# pca63557_sheet1_connectors.net
KiCad netlist of a schematic drawn in Altium Designer
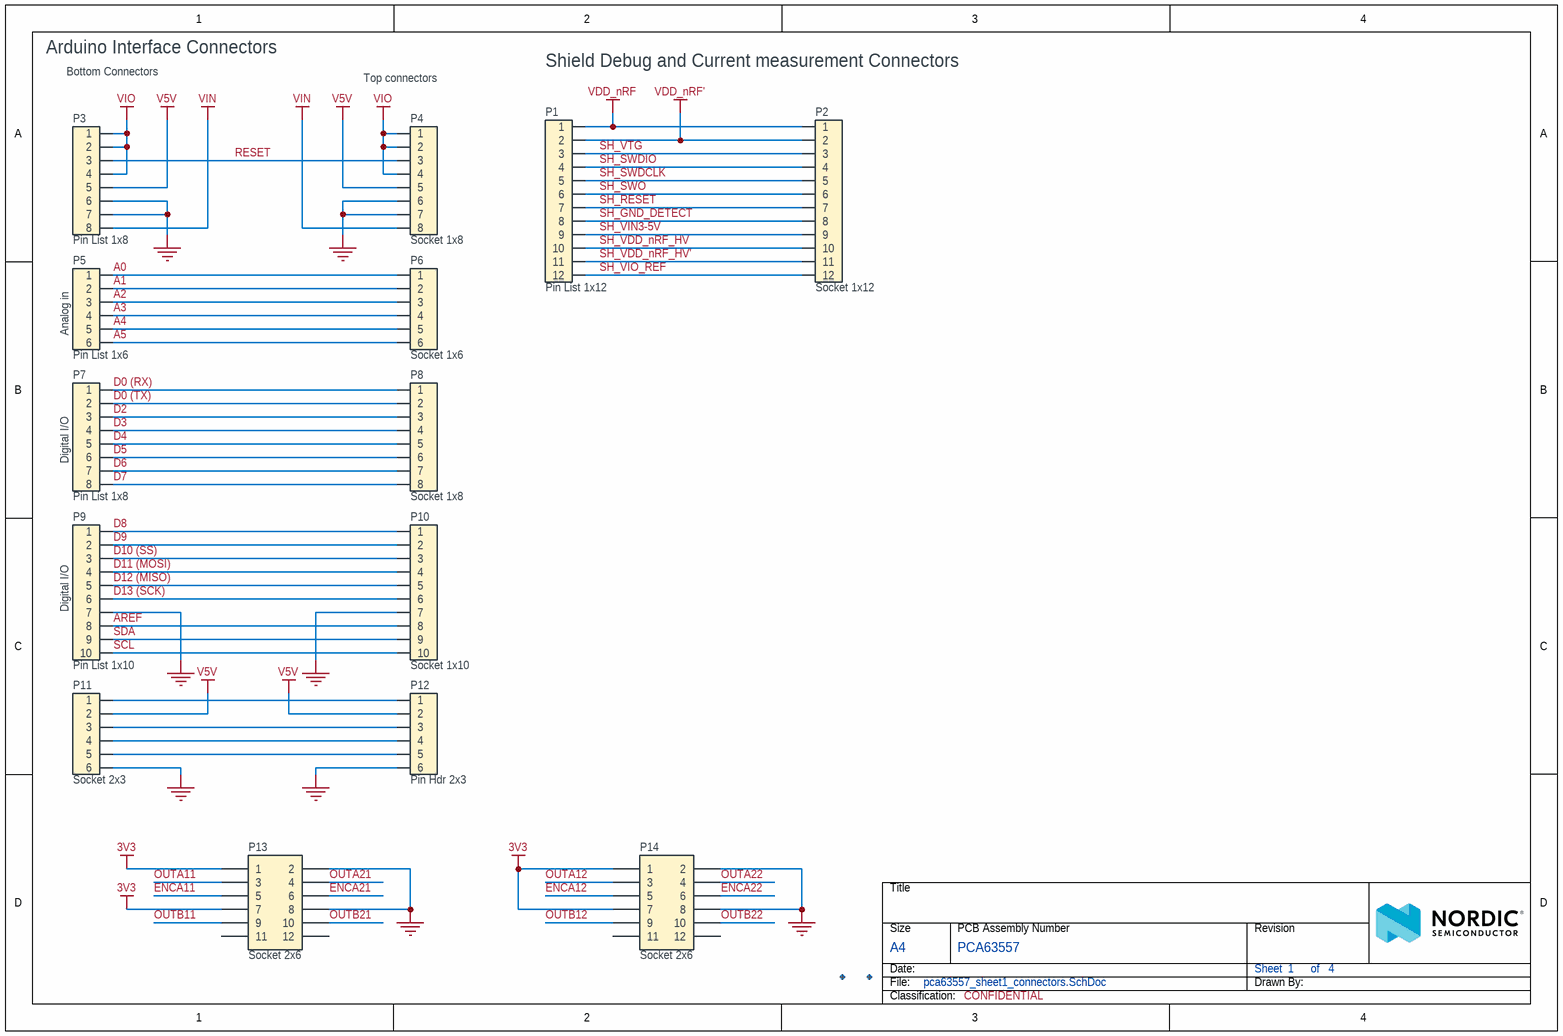
[diagram p0: pca63557_sheet1_connectors.SchDoc]

(export (version "E")
  (design (tool "Eeschema 10.0.6"))
  (components
    (comp (ref "Fid1")
      (value "Fiducial mark")
      (footprint "Fiducial")
      (description "Fiducial Mark")
      (fields
        (field (name "PART NUMBER") "Fid-Mark")
        (field (name "MANUFACTURER") "N.A.")
        (field (name "AUTHOR") "rsk")
      )
      (libsource (lib "AltiumLib") (part "Fiducial"))
    )
    (comp (ref "Fid2")
      (value "Fiducial mark")
      (footprint "Fiducial")
      (description "Fiducial Mark")
      (fields
        (field (name "PART NUMBER") "Fid-Mark")
        (field (name "MANUFACTURER") "N.A.")
        (field (name "AUTHOR") "rsk")
      )
      (libsource (lib "AltiumLib") (part "Fiducial"))
    )
    (comp (ref "P1")
      (value "Pin List 1x12")
      (footprint "LIST_1x12_SMD")
      (description "Pin List 1x12, 2.54mm (100mil), SMD")
      (fields
        (field (name "PART NUMBER") "Pin List 1x12 SMD")
        (field (name "MANUFACTURER") "W-CON")
        (field (name "AUTHOR") "rsk")
      )
      (libsource (lib "AltiumLib") (part "CONN-12"))
    )
    (comp (ref "P2")
      (value "Socket 1x12")
      (footprint "SOCKET_1x12_SMD")
      (description "Socket 1x12, 2.54mm (100mil), SMD")
      (fields
        (field (name "PART NUMBER") "Socket 1x12 SMD")
        (field (name "MANUFACTURER") "W-CON")
        (field (name "AUTHOR") "rsk")
      )
      (libsource (lib "") (part "CONN-12_1"))
    )
    (comp (ref "P3")
      (value "Pin List 1x8")
      (footprint "LIST_1x8_SMD")
      (description "Pin List 1x8, 2.54mm (100mil), SMD")
      (fields
        (field (name "PART NUMBER") "Pin List 1x8 SMD")
        (field (name "MANUFACTURER") "W-CON")
        (field (name "AUTHOR") "rsk")
      )
      (libsource (lib "") (part "CONN-8_1"))
    )
    (comp (ref "P4")
      (value "Socket 1x8")
      (footprint "SOCKET_1x8_SMD")
      (description "Socket 1x8, 2.54mm (100mil), SMD")
      (fields
        (field (name "PART NUMBER") "Socket 1x8 SMD")
        (field (name "MANUFACTURER") "W-CON")
        (field (name "AUTHOR") "rsk")
      )
      (libsource (lib "AltiumLib") (part "CONN-8"))
    )
    (comp (ref "P5")
      (value "Pin List 1x6")
      (footprint "LIST_1x6_SMD")
      (description "Pin List 1x6, 2.54mm (100mil), SMD")
      (fields
        (field (name "PART NUMBER") "Pin List 1x6 SMD")
        (field (name "MANUFACTURER") "W-CON")
        (field (name "AUTHOR") "rsk")
      )
      (libsource (lib "") (part "CONN-6_1"))
    )
    (comp (ref "P6")
      (value "Socket 1x6")
      (footprint "SOCKET_1x6_SMD")
      (description "Socket 1x6, 2.54mm (100mil), SMD")
      (fields
        (field (name "PART NUMBER") "Socket 1x6 SMD")
        (field (name "MANUFACTURER") "W-CON")
        (field (name "AUTHOR") "rsk")
      )
      (libsource (lib "AltiumLib") (part "CONN-6"))
    )
    (comp (ref "P7")
      (value "Pin List 1x8")
      (footprint "LIST_1x8_SMD")
      (description "Pin List 1x8, 2.54mm (100mil), SMD")
      (fields
        (field (name "PART NUMBER") "Pin List 1x8 SMD")
        (field (name "MANUFACTURER") "W-CON")
        (field (name "AUTHOR") "rsk")
      )
      (libsource (lib "") (part "CONN-8_1"))
    )
    (comp (ref "P8")
      (value "Socket 1x8")
      (footprint "SOCKET_1x8_SMD")
      (description "Socket 1x8, 2.54mm (100mil), SMD")
      (fields
        (field (name "PART NUMBER") "Socket 1x8 SMD")
        (field (name "MANUFACTURER") "W-CON")
        (field (name "AUTHOR") "rsk")
      )
      (libsource (lib "AltiumLib") (part "CONN-8"))
    )
    (comp (ref "P9")
      (value "Pin List 1x10")
      (footprint "LIST_1x10_SMD")
      (description "Pin List 1x10, 2.54mm (100mil), SMD")
      (fields
        (field (name "PART NUMBER") "Pin List 1x10 SMD")
        (field (name "MANUFACTURER") "W-CON")
        (field (name "AUTHOR") "rsk")
      )
      (libsource (lib "AltiumLib") (part "CONN-10"))
    )
    (comp (ref "P10")
      (value "Socket 1x10")
      (footprint "SOCKET_1x10_SMD")
      (description "Socket 1x10, 2.54mm (100mil), SMD")
      (fields
        (field (name "PART NUMBER") "Socket 1x10 SMD")
        (field (name "MANUFACTURER") "W-CON")
        (field (name "AUTHOR") "rsk")
      )
      (libsource (lib "") (part "CONN-10_1"))
    )
    (comp (ref "P11")
      (value "Socket 2x3")
      (footprint "SOCKET_2x3_SMD-2.54mm-bottom")
      (description "Socket 2x3, 2.54mm (100mil), SMD")
      (fields
        (field (name "PART NUMBER") "Socket 2x3 SMD Bottom")
        (field (name "MANUFACTURER") "W-CON")
        (field (name "AUTHOR") "rsk")
      )
      (libsource (lib "") (part "CONN-6_1"))
    )
    (comp (ref "P12")
      (value "Pin Hdr 2x3")
      (footprint "HDR_2x3-SMD")
      (description "Pin Header 2x3, 2.54mm (100mil) SMD")
      (fields
        (field (name "PART NUMBER") "Pin Header 2x3 SMD")
        (field (name "MANUFACTURER") "W-CON")
        (field (name "AUTHOR") "rsk")
      )
      (libsource (lib "AltiumLib") (part "CONN-6"))
    )
    (comp (ref "P13")
      (value "Socket 2x6")
      (footprint "SOCKET_2x6_TH_ANG_2.54")
      (description "12 Position Header Connector 0.100\" (2.54mm) Through Hole, Right Angle Gold")
      (fields
        (field (name "PART NUMBER") "Socket 2x6 SMD Right-angle")
        (field (name "MANUFACTURER") "Sullins Connector Solutions")
        (field (name "AUTHOR") "mam1")
      )
      (libsource (lib "AltiumLib") (part "CONN-2x6"))
    )
    (comp (ref "P14")
      (value "Socket 2x6")
      (footprint "SOCKET_2x6_TH_ANG_2.54")
      (description "12 Position Header Connector 0.100\" (2.54mm) Through Hole, Right Angle Gold")
      (fields
        (field (name "PART NUMBER") "Socket 2x6 SMD Right-angle")
        (field (name "MANUFACTURER") "Sullins Connector Solutions")
        (field (name "AUTHOR") "mam1")
      )
      (libsource (lib "AltiumLib") (part "CONN-2x6"))
    )
  )
  (nets
    (net (code "1") (name "/A0") (class "Default")
      (node (ref "P5") (pin "1") (pinfunction "1_1") (pintype "passive"))
      (node (ref "P6") (pin "1") (pinfunction "1_1") (pintype "passive"))
    )
    (net (code "2") (name "/A1") (class "Default")
      (node (ref "P5") (pin "2") (pinfunction "2_2") (pintype "passive"))
      (node (ref "P6") (pin "2") (pinfunction "2_2") (pintype "passive"))
    )
    (net (code "3") (name "/A2") (class "Default")
      (node (ref "P5") (pin "3") (pinfunction "3_3") (pintype "passive"))
      (node (ref "P6") (pin "3") (pinfunction "3_3") (pintype "passive"))
    )
    (net (code "4") (name "/A3") (class "Default")
      (node (ref "P5") (pin "4") (pinfunction "4_4") (pintype "passive"))
      (node (ref "P6") (pin "4") (pinfunction "4_4") (pintype "passive"))
    )
    (net (code "5") (name "/A4") (class "Default")
      (node (ref "P5") (pin "5") (pinfunction "5_5") (pintype "passive"))
      (node (ref "P6") (pin "5") (pinfunction "5_5") (pintype "passive"))
    )
    (net (code "6") (name "/A5") (class "Default")
      (node (ref "P5") (pin "6") (pinfunction "6_6") (pintype "passive"))
      (node (ref "P6") (pin "6") (pinfunction "6_6") (pintype "passive"))
    )
    (net (code "7") (name "/AREF") (class "Default")
      (node (ref "P10") (pin "8") (pinfunction "8_8") (pintype "passive"))
      (node (ref "P9") (pin "8") (pinfunction "8_8") (pintype "passive"))
    )
    (net (code "8") (name "/D0 (RX)") (class "Default")
      (node (ref "P7") (pin "1") (pinfunction "1_1") (pintype "passive"))
      (node (ref "P8") (pin "1") (pinfunction "1_1") (pintype "passive"))
    )
    (net (code "9") (name "/D0 (TX)") (class "Default")
      (node (ref "P7") (pin "2") (pinfunction "2_2") (pintype "passive"))
      (node (ref "P8") (pin "2") (pinfunction "2_2") (pintype "passive"))
    )
    (net (code "10") (name "/D2") (class "Default")
      (node (ref "P7") (pin "3") (pinfunction "3_3") (pintype "passive"))
      (node (ref "P8") (pin "3") (pinfunction "3_3") (pintype "passive"))
    )
    (net (code "11") (name "/D3") (class "Default")
      (node (ref "P7") (pin "4") (pinfunction "4_4") (pintype "passive"))
      (node (ref "P8") (pin "4") (pinfunction "4_4") (pintype "passive"))
    )
    (net (code "12") (name "/D4") (class "Default")
      (node (ref "P7") (pin "5") (pinfunction "5_5") (pintype "passive"))
      (node (ref "P8") (pin "5") (pinfunction "5_5") (pintype "passive"))
    )
    (net (code "13") (name "/D5") (class "Default")
      (node (ref "P7") (pin "6") (pinfunction "6_6") (pintype "passive"))
      (node (ref "P8") (pin "6") (pinfunction "6_6") (pintype "passive"))
    )
    (net (code "14") (name "/D6") (class "Default")
      (node (ref "P7") (pin "7") (pinfunction "7_7") (pintype "passive"))
      (node (ref "P8") (pin "7") (pinfunction "7_7") (pintype "passive"))
    )
    (net (code "15") (name "/D7") (class "Default")
      (node (ref "P7") (pin "8") (pinfunction "8_8") (pintype "passive"))
      (node (ref "P8") (pin "8") (pinfunction "8_8") (pintype "passive"))
    )
    (net (code "16") (name "/D8") (class "Default")
      (node (ref "P10") (pin "1") (pinfunction "1_1") (pintype "passive"))
      (node (ref "P9") (pin "1") (pinfunction "1_1") (pintype "passive"))
    )
    (net (code "17") (name "/D9") (class "Default")
      (node (ref "P10") (pin "2") (pinfunction "2_2") (pintype "passive"))
      (node (ref "P9") (pin "2") (pinfunction "2_2") (pintype "passive"))
    )
    (net (code "18") (name "/D10 (SS)") (class "Default")
      (node (ref "P10") (pin "3") (pinfunction "3_3") (pintype "passive"))
      (node (ref "P9") (pin "3") (pinfunction "3_3") (pintype "passive"))
    )
    (net (code "19") (name "/D11 (MOSI)") (class "Default")
      (node (ref "P10") (pin "4") (pinfunction "4_4") (pintype "passive"))
      (node (ref "P9") (pin "4") (pinfunction "4_4") (pintype "passive"))
    )
    (net (code "20") (name "/D12 (MISO)") (class "Default")
      (node (ref "P10") (pin "5") (pinfunction "5_5") (pintype "passive"))
      (node (ref "P9") (pin "5") (pinfunction "5_5") (pintype "passive"))
    )
    (net (code "21") (name "/D13 (SCK)") (class "Default")
      (node (ref "P10") (pin "6") (pinfunction "6_6") (pintype "passive"))
      (node (ref "P9") (pin "6") (pinfunction "6_6") (pintype "passive"))
    )
    (net (code "22") (name "/ENCA11") (class "Default")
      (node (ref "P13") (pin "5") (pinfunction "5_5") (pintype "passive"))
    )
    (net (code "23") (name "/ENCA12") (class "Default")
      (node (ref "P14") (pin "5") (pinfunction "5_5") (pintype "passive"))
    )
    (net (code "24") (name "/ENCA21") (class "Default")
      (node (ref "P13") (pin "6") (pinfunction "6_6") (pintype "passive"))
    )
    (net (code "25") (name "/ENCA22") (class "Default")
      (node (ref "P14") (pin "6") (pinfunction "6_6") (pintype "passive"))
    )
    (net (code "26") (name "/OUTA11") (class "Default")
      (node (ref "P13") (pin "3") (pinfunction "3_3") (pintype "passive"))
    )
    (net (code "27") (name "/OUTA12") (class "Default")
      (node (ref "P14") (pin "3") (pinfunction "3_3") (pintype "passive"))
    )
    (net (code "28") (name "/OUTA21") (class "Default")
      (node (ref "P13") (pin "4") (pinfunction "4_4") (pintype "passive"))
    )
    (net (code "29") (name "/OUTA22") (class "Default")
      (node (ref "P14") (pin "4") (pinfunction "4_4") (pintype "passive"))
    )
    (net (code "30") (name "/OUTB11") (class "Default")
      (node (ref "P13") (pin "9") (pinfunction "9_9") (pintype "passive"))
    )
    (net (code "31") (name "/OUTB12") (class "Default")
      (node (ref "P14") (pin "9") (pinfunction "9_9") (pintype "passive"))
    )
    (net (code "32") (name "/OUTB21") (class "Default")
      (node (ref "P13") (pin "10") (pinfunction "10_10") (pintype "passive"))
    )
    (net (code "33") (name "/OUTB22") (class "Default")
      (node (ref "P14") (pin "10") (pinfunction "10_10") (pintype "passive"))
    )
    (net (code "34") (name "/RESET") (class "Default")
      (node (ref "P3") (pin "3") (pinfunction "3_3") (pintype "passive"))
      (node (ref "P4") (pin "3") (pinfunction "3_3") (pintype "passive"))
    )
    (net (code "35") (name "/SCL") (class "Default")
      (node (ref "P10") (pin "10") (pinfunction "10_10") (pintype "passive"))
      (node (ref "P9") (pin "10") (pinfunction "10_10") (pintype "passive"))
    )
    (net (code "36") (name "/SDA") (class "Default")
      (node (ref "P10") (pin "9") (pinfunction "9_9") (pintype "passive"))
      (node (ref "P9") (pin "9") (pinfunction "9_9") (pintype "passive"))
    )
    (net (code "37") (name "/SH_GND_DETECT") (class "Default")
      (node (ref "P1") (pin "8") (pinfunction "8_8") (pintype "passive"))
      (node (ref "P2") (pin "8") (pinfunction "8_8") (pintype "passive"))
    )
    (net (code "38") (name "/SH_RESET") (class "Default")
      (node (ref "P1") (pin "7") (pinfunction "7_7") (pintype "passive"))
      (node (ref "P2") (pin "7") (pinfunction "7_7") (pintype "passive"))
    )
    (net (code "39") (name "/SH_SWDCLK") (class "Default")
      (node (ref "P1") (pin "5") (pinfunction "5_5") (pintype "passive"))
      (node (ref "P2") (pin "5") (pinfunction "5_5") (pintype "passive"))
    )
    (net (code "40") (name "/SH_SWDIO") (class "Default")
      (node (ref "P1") (pin "4") (pinfunction "4_4") (pintype "passive"))
      (node (ref "P2") (pin "4") (pinfunction "4_4") (pintype "passive"))
    )
    (net (code "41") (name "/SH_SWO") (class "Default")
      (node (ref "P1") (pin "6") (pinfunction "6_6") (pintype "passive"))
      (node (ref "P2") (pin "6") (pinfunction "6_6") (pintype "passive"))
    )
    (net (code "42") (name "/SH_VDD_nRF_HV") (class "Default")
      (node (ref "P1") (pin "10") (pinfunction "10_10") (pintype "passive"))
      (node (ref "P2") (pin "10") (pinfunction "10_10") (pintype "passive"))
    )
    (net (code "43") (name "/SH_VDD_nRF_HV'") (class "Default")
      (node (ref "P1") (pin "11") (pinfunction "11_11") (pintype "passive"))
      (node (ref "P2") (pin "11") (pinfunction "11_11") (pintype "passive"))
    )
    (net (code "44") (name "/SH_VIN3-5V") (class "Default")
      (node (ref "P1") (pin "9") (pinfunction "9_9") (pintype "passive"))
      (node (ref "P2") (pin "9") (pinfunction "9_9") (pintype "passive"))
    )
    (net (code "45") (name "/SH_VIO_REF") (class "Default")
      (node (ref "P1") (pin "12") (pinfunction "12_12") (pintype "passive"))
      (node (ref "P2") (pin "12") (pinfunction "12_12") (pintype "passive"))
    )
    (net (code "46") (name "/SH_VTG") (class "Default")
      (node (ref "P1") (pin "3") (pinfunction "3_3") (pintype "passive"))
      (node (ref "P2") (pin "3") (pinfunction "3_3") (pintype "passive"))
    )
    (net (code "47") (name "3V3") (class "Default")
      (node (ref "P13") (pin "1") (pinfunction "1_1") (pintype "passive"))
      (node (ref "P13") (pin "7") (pinfunction "7_7") (pintype "passive"))
      (node (ref "P14") (pin "1") (pinfunction "1_1") (pintype "passive"))
      (node (ref "P14") (pin "7") (pinfunction "7_7") (pintype "passive"))
    )
    (net (code "48") (name "GND") (class "Default")
      (node (ref "P10") (pin "7") (pinfunction "7_7") (pintype "passive"))
      (node (ref "P11") (pin "6") (pinfunction "6_6") (pintype "passive"))
      (node (ref "P12") (pin "6") (pinfunction "6_6") (pintype "passive"))
      (node (ref "P13") (pin "2") (pinfunction "2_2") (pintype "passive"))
      (node (ref "P13") (pin "8") (pinfunction "8_8") (pintype "passive"))
      (node (ref "P14") (pin "2") (pinfunction "2_2") (pintype "passive"))
      (node (ref "P14") (pin "8") (pinfunction "8_8") (pintype "passive"))
      (node (ref "P3") (pin "6") (pinfunction "6_6") (pintype "passive"))
      (node (ref "P3") (pin "7") (pinfunction "7_7") (pintype "passive"))
      (node (ref "P4") (pin "6") (pinfunction "6_6") (pintype "passive"))
      (node (ref "P4") (pin "7") (pinfunction "7_7") (pintype "passive"))
      (node (ref "P9") (pin "7") (pinfunction "7_7") (pintype "passive"))
    )
    (net (code "49") (name "Net-(P11-Pad1)") (class "Default")
      (node (ref "P11") (pin "1") (pinfunction "1_1") (pintype "passive"))
      (node (ref "P12") (pin "1") (pinfunction "1_1") (pintype "passive"))
    )
    (net (code "50") (name "Net-(P11-Pad3)") (class "Default")
      (node (ref "P11") (pin "3") (pinfunction "3_3") (pintype "passive"))
      (node (ref "P12") (pin "3") (pinfunction "3_3") (pintype "passive"))
    )
    (net (code "51") (name "Net-(P11-Pad4)") (class "Default")
      (node (ref "P11") (pin "4") (pinfunction "4_4") (pintype "passive"))
      (node (ref "P12") (pin "4") (pinfunction "4_4") (pintype "passive"))
    )
    (net (code "52") (name "Net-(P11-Pad5)") (class "Default")
      (node (ref "P11") (pin "5") (pinfunction "5_5") (pintype "passive"))
      (node (ref "P12") (pin "5") (pinfunction "5_5") (pintype "passive"))
    )
    (net (code "53") (name "V5V") (class "Default")
      (node (ref "P11") (pin "2") (pinfunction "2_2") (pintype "passive"))
      (node (ref "P12") (pin "2") (pinfunction "2_2") (pintype "passive"))
      (node (ref "P3") (pin "5") (pinfunction "5_5") (pintype "passive"))
      (node (ref "P4") (pin "5") (pinfunction "5_5") (pintype "passive"))
    )
    (net (code "54") (name "VDD_nRF") (class "Default")
      (node (ref "P1") (pin "1") (pinfunction "1_1") (pintype "passive"))
      (node (ref "P2") (pin "1") (pinfunction "1_1") (pintype "passive"))
    )
    (net (code "55") (name "VDD_nRF'") (class "Default")
      (node (ref "P1") (pin "2") (pinfunction "2_2") (pintype "passive"))
      (node (ref "P2") (pin "2") (pinfunction "2_2") (pintype "passive"))
    )
    (net (code "56") (name "VIN") (class "Default")
      (node (ref "P3") (pin "8") (pinfunction "8_8") (pintype "passive"))
      (node (ref "P4") (pin "8") (pinfunction "8_8") (pintype "passive"))
    )
    (net (code "57") (name "VIO") (class "Default")
      (node (ref "P3") (pin "1") (pinfunction "1_1") (pintype "passive"))
      (node (ref "P3") (pin "2") (pinfunction "2_2") (pintype "passive"))
      (node (ref "P3") (pin "4") (pinfunction "4_4") (pintype "passive"))
      (node (ref "P4") (pin "1") (pinfunction "1_1") (pintype "passive"))
      (node (ref "P4") (pin "2") (pinfunction "2_2") (pintype "passive"))
      (node (ref "P4") (pin "4") (pinfunction "4_4") (pintype "passive"))
    )
    (net (code "58") (name "unconnected-(P13-Pad11)") (class "Default")
      (node (ref "P13") (pin "11") (pinfunction "11_11") (pintype "passive"))
    )
    (net (code "59") (name "unconnected-(P13-Pad12)") (class "Default")
      (node (ref "P13") (pin "12") (pinfunction "12_12") (pintype "passive"))
    )
    (net (code "60") (name "unconnected-(P14-Pad11)") (class "Default")
      (node (ref "P14") (pin "11") (pinfunction "11_11") (pintype "passive"))
    )
    (net (code "61") (name "unconnected-(P14-Pad12)") (class "Default")
      (node (ref "P14") (pin "12") (pinfunction "12_12") (pintype "passive"))
    )
  )
)
